# Sheet2.net
KiCad netlist of a schematic drawn in Altium Designer
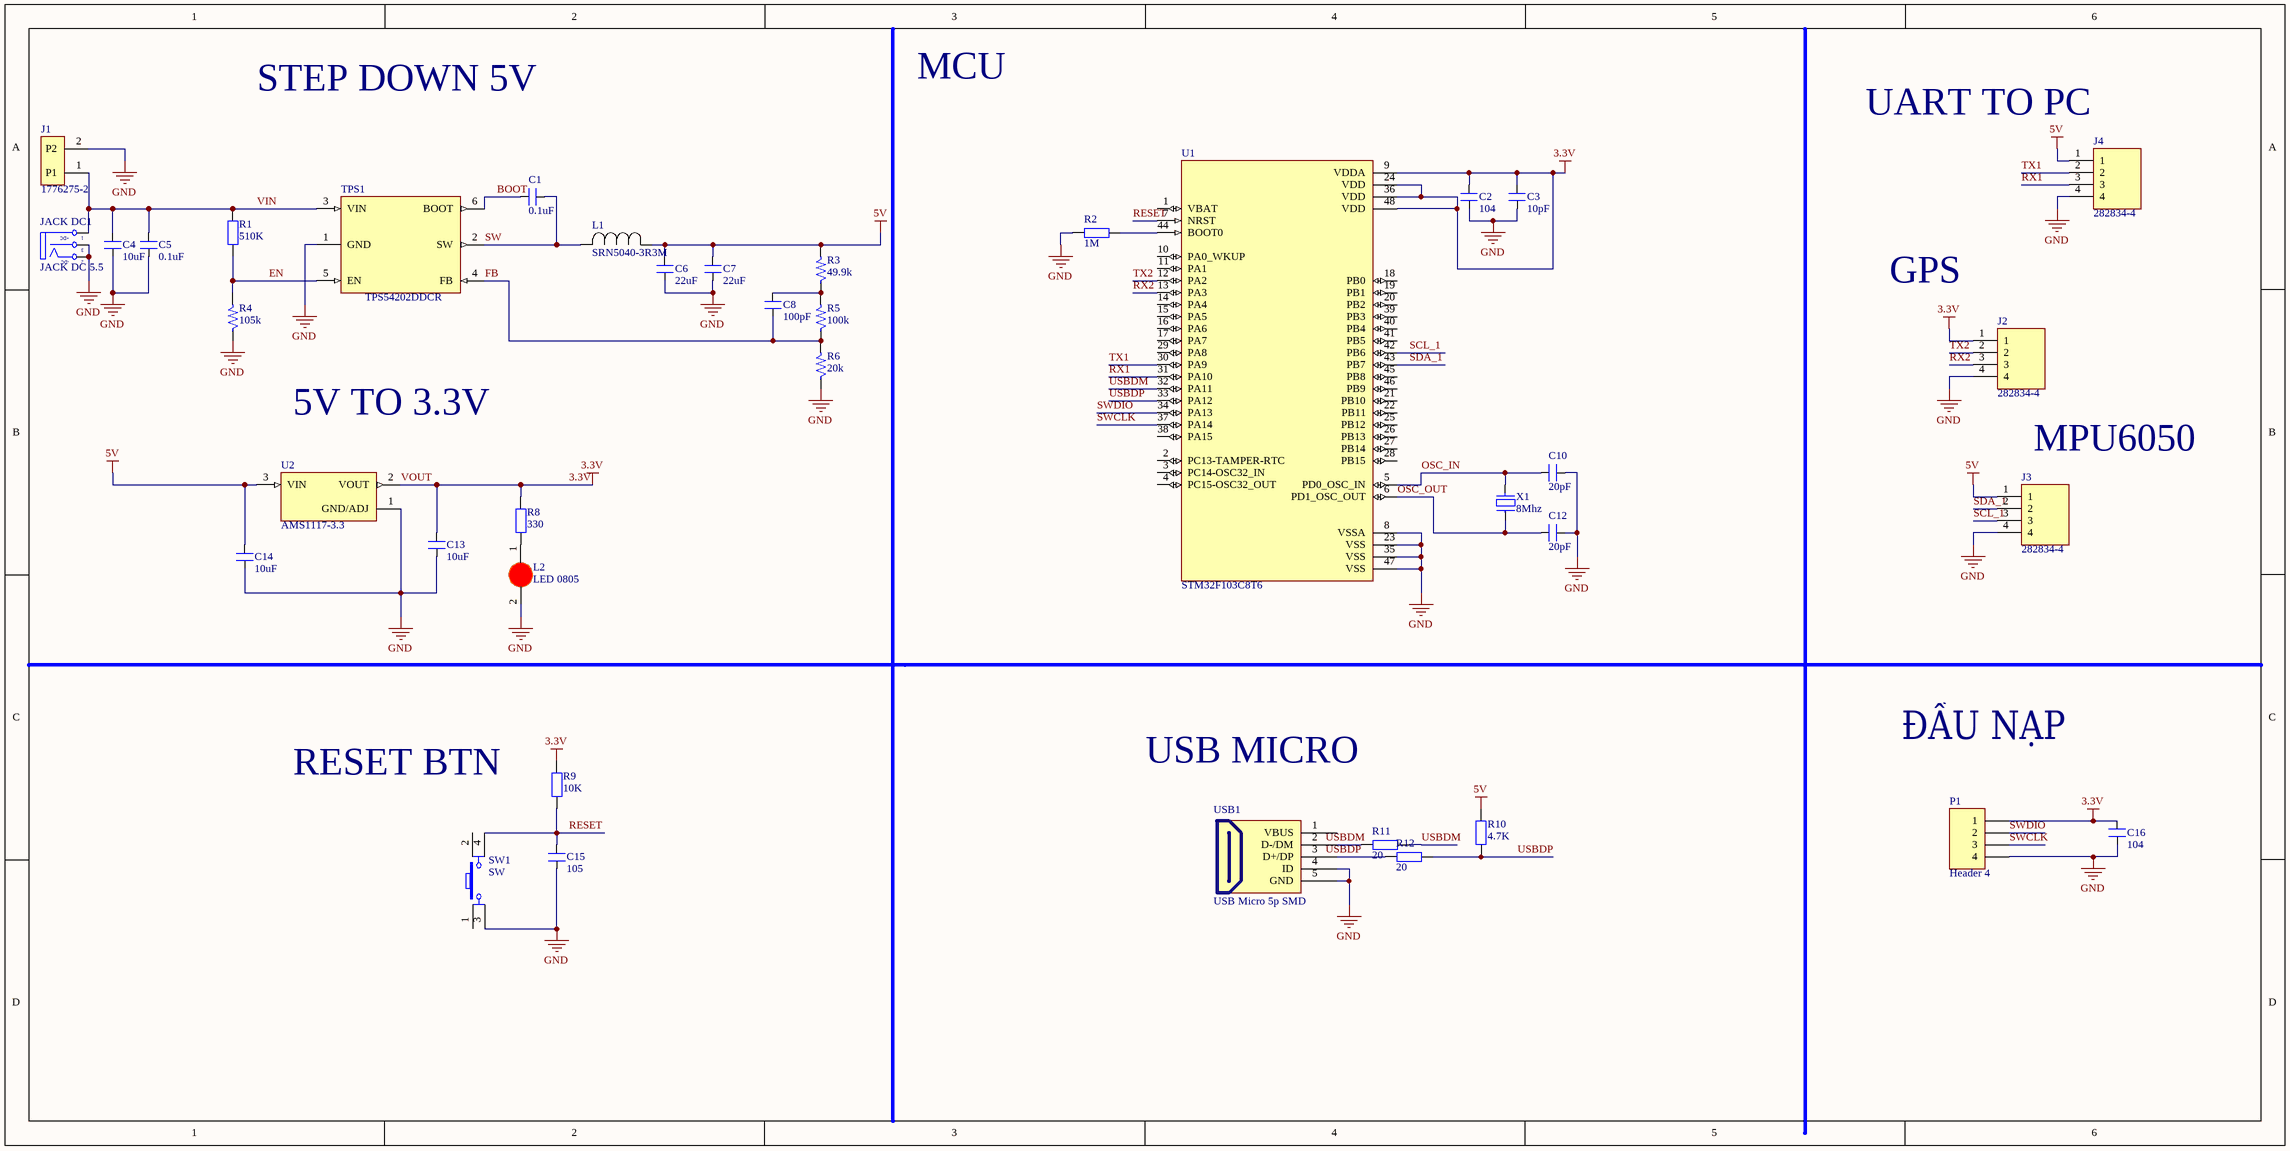
[diagram p0: Sheet2.SchDoc]

(export (version "E")
  (design (tool "Eeschema 10.0.6"))
  (components
    (comp (ref "C1")
      (value "0.1uF")
      (footprint "SM-0805")
      (description "Cap SMD")
      (libsource (lib "syhaunguyen") (part "CM"))
    )
    (comp (ref "C2")
      (value "104")
      (footprint "SM-0805")
      (description "Cap SMD")
      (libsource (lib "syhaunguyen") (part "CM"))
    )
    (comp (ref "C3")
      (value "10pF")
      (footprint "SM-0805")
      (description "Cap SMD")
      (libsource (lib "syhaunguyen") (part "CM"))
    )
    (comp (ref "C4")
      (value "10uF")
      (footprint "SM-0805")
      (description "Cap SMD")
      (libsource (lib "syhaunguyen") (part "CM"))
    )
    (comp (ref "C5")
      (value "0.1uF")
      (footprint "SM-0805")
      (description "Cap SMD")
      (libsource (lib "syhaunguyen") (part "CM"))
    )
    (comp (ref "C6")
      (value "22uF")
      (footprint "SM-0805")
      (description "Cap SMD")
      (libsource (lib "syhaunguyen") (part "CM"))
    )
    (comp (ref "C7")
      (value "22uF")
      (footprint "SM-0805")
      (description "Cap SMD")
      (libsource (lib "syhaunguyen") (part "CM"))
    )
    (comp (ref "C8")
      (value "100pF")
      (footprint "SM-0805")
      (description "Cap SMD")
      (libsource (lib "syhaunguyen") (part "CM"))
    )
    (comp (ref "C10")
      (value "20pF")
      (footprint "SM-0805")
      (description "Cap SMD")
      (libsource (lib "syhaunguyen") (part "CM"))
    )
    (comp (ref "C12")
      (value "20pF")
      (footprint "SM-0805")
      (description "Cap SMD")
      (libsource (lib "syhaunguyen") (part "CM"))
    )
    (comp (ref "C13")
      (value "10uF")
      (footprint "SM-0805")
      (description "Cap SMD")
      (libsource (lib "syhaunguyen") (part "CM"))
    )
    (comp (ref "C14")
      (value "10uF")
      (footprint "SM-0805")
      (description "Cap SMD")
      (libsource (lib "syhaunguyen") (part "CM"))
    )
    (comp (ref "C15")
      (value "105")
      (footprint "SM-0805")
      (description "Cap SMD")
      (libsource (lib "syhaunguyen") (part "CM"))
    )
    (comp (ref "C16")
      (value "104")
      (footprint "SM-0805")
      (description "Cap SMD")
      (libsource (lib "syhaunguyen") (part "CM"))
    )
    (comp (ref "J1")
      (value "1776275-2")
      (footprint "TE_1776275-2")
      (description "2 Position Wire to Board Terminal Block Horizontal with Board 0.138\" (3.50mm) Through Hole")
      (fields (field (name "MF") "TE Connectivity"))
      (libsource (lib "1776275-2") (part "1776275-2"))
    )
    (comp (ref "J2")
      (value "282834-4")
      (footprint "TE_282834-4")
      (description "4 Position Wire to Board Terminal Block Horizontal with Board 0.100 (2.54mm) Through Hole")
      (fields (field (name "MF") "TE Connectivity"))
      (libsource (lib "282834-4") (part "282834-4"))
    )
    (comp (ref "J3")
      (value "282834-4")
      (footprint "TE_282834-4")
      (description "4 Position Wire to Board Terminal Block Horizontal with Board 0.100 (2.54mm) Through Hole")
      (fields (field (name "MF") "TE Connectivity"))
      (libsource (lib "282834-4") (part "282834-4"))
    )
    (comp (ref "J4")
      (value "282834-4")
      (footprint "TE_282834-4")
      (description "4 Position Wire to Board Terminal Block Horizontal with Board 0.100 (2.54mm) Through Hole")
      (fields (field (name "MF") "TE Connectivity"))
      (libsource (lib "282834-4") (part "282834-4"))
    )
    (comp (ref "JACK DC1")
      (value "JACK DC 5.5")
      (footprint "JACK DC 5.5")
      (libsource (lib "Altium_Lib_by_KhueNguyenCreator") (part "JACK DC 5.5"))
    )
    (comp (ref "L1")
      (value "SRN5040-3R3M")
      (footprint "IND_SRN5040_BRN")
      (description "No Description Available")
      (libsource (lib "SRN5040-3R3M") (part "SRN5040-3R3M"))
    )
    (comp (ref "L2")
      (value "LED 0805")
      (footprint "LED-0805-Red")
      (description "Dán")
      (libsource (lib "Altium_Lib_by_KhueNguyenCreator") (part "LED 0805 Do"))
    )
    (comp (ref "P1")
      (value "Header 4")
      (footprint "HDR1X4")
      (description "Header, 4-Pin")
      (fields (field (name "PUBLISHER") "Altium Limited"))
      (libsource (lib "Miscellaneous Connectors") (part "Header 4"))
    )
    (comp (ref "R1")
      (value "510K")
      (footprint "SM-0805")
      (description "Resistor SMD")
      (libsource (lib "syhaunguyen") (part "RM"))
    )
    (comp (ref "R2")
      (value "1M")
      (footprint "0805 res")
      (description "Resistor SMD")
      (libsource (lib "syhaunguyen") (part "RM"))
    )
    (comp (ref "R3")
      (value "49.9k")
      (footprint "0805 res")
      (description "Resistor 1/4W")
      (libsource (lib "syhaunguyen") (part "res0805"))
    )
    (comp (ref "R4")
      (value "105k")
      (footprint "0805 res")
      (description "Resistor 1/4W")
      (libsource (lib "syhaunguyen") (part "res0805"))
    )
    (comp (ref "R5")
      (value "100k")
      (footprint "0805 res")
      (description "Resistor 1/4W")
      (libsource (lib "syhaunguyen") (part "res0805"))
    )
    (comp (ref "R6")
      (value "20k")
      (footprint "0805 res")
      (description "Resistor 1/4W")
      (libsource (lib "syhaunguyen") (part "res0805"))
    )
    (comp (ref "R8")
      (value "330")
      (footprint "0805 res")
      (description "Resistor SMD")
      (libsource (lib "syhaunguyen") (part "RM"))
    )
    (comp (ref "R9")
      (value "10K")
      (footprint "0805 res")
      (description "Resistor SMD")
      (libsource (lib "syhaunguyen") (part "RM"))
    )
    (comp (ref "R10")
      (value "4.7K")
      (footprint "0805 res")
      (description "Resistor SMD")
      (libsource (lib "syhaunguyen") (part "RM"))
    )
    (comp (ref "R11")
      (value "20")
      (footprint "0805 res")
      (description "Resistor SMD")
      (libsource (lib "syhaunguyen") (part "RM"))
    )
    (comp (ref "R12")
      (value "20")
      (footprint "0805 res")
      (description "Resistor SMD")
      (libsource (lib "syhaunguyen") (part "RM"))
    )
    (comp (ref "SW1")
      (value "SW")
      (footprint "SW4")
      (description "Switch button 4 pin")
      (libsource (lib "syhaunguyen") (part "SW4"))
    )
    (comp (ref "TPS1")
      (value "TPS54202DDCR")
      (footprint "SOT95P280X110-6N")
      (fields
        (field (name "MF") "Texas Instruments")
        (field (name "BUYPART") "https://www.snapeda.com/parts/TPS54202DDCR/Texas%20Instruments/view-part/565860/?ref=eda")
      )
      (libsource (lib "TPS54202DDCR") (part "TPS54202DDCR"))
    )
    (comp (ref "U1")
      (value "STM32F103C8T6")
      (footprint "QFP50P900X900X160-48N")
      (description "ARM® Cortex®-M3 STM32F1 Microcontroller IC 32-Bit 72MHz 64KB (64K x 8) FLASH 48-LQFP (7x7)")
      (fields (field (name "MF") "STMicroelectronics"))
      (libsource (lib "STM32F103C8T6") (part "STM32F103C8T6"))
    )
    (comp (ref "U2")
      (value "AMS1117-3.3")
      (footprint "SOT229P700X180-4N")
      (description "Sot223/Pkg 1-Amp 3.3-Volt Low Drop Out Voltage Regulatator")
      (fields (field (name "MF") "Advanced Monolithic Systems"))
      (libsource (lib "AMS1117-3.3") (part "AMS1117-3.3"))
    )
    (comp (ref "USB1")
      (value "USB Micro 5p SMD")
      (footprint "USB Micro 5p SMD")
      (description "USB Type B")
      (libsource (lib "Altium_Lib_by_KhueNguyenCreator") (part "USB Micro 5p SMD"))
    )
    (comp (ref "X1")
      (value "8Mhz")
      (footprint "VioletofSun:XT2")
      (description "Crystal For all Crystal 2pin.")
      (libsource (lib "VioletofSun") (part "XT2"))
    )
  )
  (nets
    (net (code "1") (name "/BOOT") (class "Default")
      (node (ref "C1") (pin "2") (pinfunction "2_2") (pintype "passive"))
      (node (ref "TPS1") (pin "6") (pinfunction "BOOT_6") (pintype "output"))
    )
    (net (code "2") (name "/EN") (class "Default")
      (node (ref "R1") (pin "2") (pinfunction "2_2") (pintype "passive"))
      (node (ref "R4") (pin "2") (pinfunction "2_2") (pintype "passive"))
      (node (ref "TPS1") (pin "5") (pinfunction "EN_5") (pintype "input"))
    )
    (net (code "3") (name "/FB") (class "Default")
      (node (ref "C8") (pin "1") (pinfunction "1_1") (pintype "passive"))
      (node (ref "R5") (pin "1") (pinfunction "1_1") (pintype "passive"))
      (node (ref "R6") (pin "2") (pinfunction "2_2") (pintype "passive"))
      (node (ref "TPS1") (pin "4") (pinfunction "FB_4") (pintype "input"))
    )
    (net (code "4") (name "/OSC_IN") (class "Default")
      (node (ref "C10") (pin "2") (pinfunction "2_2") (pintype "passive"))
      (node (ref "U1") (pin "5") (pinfunction "PD0_OSC_IN_5") (pintype "bidirectional"))
      (node (ref "X1") (pin "2") (pinfunction "2_2") (pintype "passive"))
    )
    (net (code "5") (name "/OSC_OUT") (class "Default")
      (node (ref "C12") (pin "2") (pinfunction "2_2") (pintype "passive"))
      (node (ref "U1") (pin "6") (pinfunction "PD1_OSC_OUT_6") (pintype "bidirectional"))
      (node (ref "X1") (pin "1") (pinfunction "1_1") (pintype "passive"))
    )
    (net (code "6") (name "/RESET") (class "Default")
      (node (ref "C15") (pin "2") (pinfunction "2_2") (pintype "passive"))
      (node (ref "R9") (pin "1") (pinfunction "1_1") (pintype "passive"))
      (node (ref "SW1") (pin "4") (pintype "passive"))
      (node (ref "U1") (pin "7") (pinfunction "NRST_7") (pintype "input"))
    )
    (net (code "7") (name "/RX1") (class "Default")
      (node (ref "J4") (pin "3") (pinfunction "3_3") (pintype "passive"))
      (node (ref "U1") (pin "31") (pinfunction "PA10_31") (pintype "bidirectional"))
    )
    (net (code "8") (name "/RX2") (class "Default")
      (node (ref "J2") (pin "3") (pinfunction "3_3") (pintype "passive"))
      (node (ref "U1") (pin "13") (pinfunction "PA3_13") (pintype "bidirectional"))
    )
    (net (code "9") (name "/SCL_1") (class "Default")
      (node (ref "J3") (pin "3") (pinfunction "3_3") (pintype "passive"))
      (node (ref "U1") (pin "42") (pinfunction "PB6_42") (pintype "bidirectional"))
    )
    (net (code "10") (name "/SDA_1") (class "Default")
      (node (ref "J3") (pin "2") (pinfunction "2_2") (pintype "passive"))
      (node (ref "U1") (pin "43") (pinfunction "PB7_43") (pintype "bidirectional"))
    )
    (net (code "11") (name "/SW") (class "Default")
      (node (ref "C1") (pin "1") (pinfunction "1_1") (pintype "passive"))
      (node (ref "L1") (pin "2") (pinfunction "2_2") (pintype "passive"))
      (node (ref "TPS1") (pin "2") (pinfunction "SW_2") (pintype "output"))
    )
    (net (code "12") (name "/SWCLK") (class "Default")
      (node (ref "P1") (pin "3") (pinfunction "3_3") (pintype "passive"))
      (node (ref "U1") (pin "37") (pinfunction "PA14_37") (pintype "bidirectional"))
    )
    (net (code "13") (name "/SWDIO") (class "Default")
      (node (ref "P1") (pin "2") (pinfunction "2_2") (pintype "passive"))
      (node (ref "U1") (pin "34") (pinfunction "PA13_34") (pintype "bidirectional"))
    )
    (net (code "14") (name "/TX1") (class "Default")
      (node (ref "J4") (pin "2") (pinfunction "2_2") (pintype "passive"))
      (node (ref "U1") (pin "30") (pinfunction "PA9_30") (pintype "bidirectional"))
    )
    (net (code "15") (name "/TX2") (class "Default")
      (node (ref "J2") (pin "2") (pinfunction "2_2") (pintype "passive"))
      (node (ref "U1") (pin "12") (pinfunction "PA2_12") (pintype "bidirectional"))
    )
    (net (code "16") (name "/USBDM") (class "Default")
      (node (ref "R11") (pin "2") (pinfunction "2_2") (pintype "passive"))
      (node (ref "U1") (pin "32") (pinfunction "PA11_32") (pintype "bidirectional"))
    )
    (net (code "17") (name "/USBDP") (class "Default")
      (node (ref "R10") (pin "1") (pinfunction "1_1") (pintype "passive"))
      (node (ref "R12") (pin "2") (pinfunction "2_2") (pintype "passive"))
      (node (ref "U1") (pin "33") (pinfunction "PA12_33") (pintype "bidirectional"))
    )
    (net (code "18") (name "/VIN") (class "Default")
      (node (ref "C4") (pin "2") (pinfunction "2_2") (pintype "passive"))
      (node (ref "C5") (pin "2") (pinfunction "2_2") (pintype "passive"))
      (node (ref "J1") (pin "1") (pinfunction "P1_1") (pintype "passive"))
      (node (ref "JACK DC1") (pin "1") (pinfunction "T_1") (pintype "passive"))
      (node (ref "R1") (pin "1") (pinfunction "1_1") (pintype "passive"))
      (node (ref "TPS1") (pin "3") (pinfunction "VIN_3") (pintype "input"))
    )
    (net (code "19") (name "3.3V") (class "Default")
      (node (ref "C13") (pin "2") (pinfunction "2_2") (pintype "passive"))
      (node (ref "C16") (pin "1") (pinfunction "1_1") (pintype "passive"))
      (node (ref "C2") (pin "2") (pinfunction "2_2") (pintype "passive"))
      (node (ref "C3") (pin "2") (pinfunction "2_2") (pintype "passive"))
      (node (ref "J2") (pin "1") (pinfunction "1_1") (pintype "passive"))
      (node (ref "P1") (pin "1") (pinfunction "1_1") (pintype "passive"))
      (node (ref "R8") (pin "2") (pinfunction "2_2") (pintype "passive"))
      (node (ref "R9") (pin "2") (pinfunction "2_2") (pintype "passive"))
      (node (ref "U1") (pin "24") (pinfunction "VDD_24") (pintype "power_in"))
      (node (ref "U1") (pin "36") (pinfunction "VDD_36") (pintype "power_in"))
      (node (ref "U1") (pin "48") (pinfunction "VDD_48") (pintype "power_in"))
      (node (ref "U1") (pin "9") (pinfunction "VDDA_9") (pintype "power_in"))
      (node (ref "U2") (pin "2") (pinfunction "VOUT_2") (pintype "output"))
    )
    (net (code "20") (name "5V") (class "Default")
      (node (ref "C14") (pin "2") (pinfunction "2_2") (pintype "passive"))
      (node (ref "C6") (pin "2") (pinfunction "2_2") (pintype "passive"))
      (node (ref "C7") (pin "2") (pinfunction "2_2") (pintype "passive"))
      (node (ref "J3") (pin "1") (pinfunction "1_1") (pintype "passive"))
      (node (ref "J4") (pin "1") (pinfunction "1_1") (pintype "passive"))
      (node (ref "L1") (pin "1") (pinfunction "1_1") (pintype "passive"))
      (node (ref "R10") (pin "2") (pinfunction "2_2") (pintype "passive"))
      (node (ref "R3") (pin "2") (pinfunction "2_2") (pintype "passive"))
      (node (ref "U2") (pin "3") (pinfunction "VIN_3") (pintype "input"))
    )
    (net (code "21") (name "GND") (class "Default")
      (node (ref "C10") (pin "1") (pinfunction "1_1") (pintype "passive"))
      (node (ref "C12") (pin "1") (pinfunction "1_1") (pintype "passive"))
      (node (ref "C13") (pin "1") (pinfunction "1_1") (pintype "passive"))
      (node (ref "C14") (pin "1") (pinfunction "1_1") (pintype "passive"))
      (node (ref "C15") (pin "1") (pinfunction "1_1") (pintype "passive"))
      (node (ref "C16") (pin "2") (pinfunction "2_2") (pintype "passive"))
      (node (ref "C2") (pin "1") (pinfunction "1_1") (pintype "passive"))
      (node (ref "C3") (pin "1") (pinfunction "1_1") (pintype "passive"))
      (node (ref "C4") (pin "1") (pinfunction "1_1") (pintype "passive"))
      (node (ref "C5") (pin "1") (pinfunction "1_1") (pintype "passive"))
      (node (ref "C6") (pin "1") (pinfunction "1_1") (pintype "passive"))
      (node (ref "C7") (pin "1") (pinfunction "1_1") (pintype "passive"))
      (node (ref "J1") (pin "2") (pinfunction "P2_2") (pintype "passive"))
      (node (ref "J2") (pin "4") (pinfunction "4_4") (pintype "passive"))
      (node (ref "J3") (pin "4") (pinfunction "4_4") (pintype "passive"))
      (node (ref "J4") (pin "4") (pinfunction "4_4") (pintype "passive"))
      (node (ref "JACK DC1") (pin "2") (pinfunction "TN_2") (pintype "passive"))
      (node (ref "JACK DC1") (pin "3") (pinfunction "S_3") (pintype "power_in"))
      (node (ref "L2") (pin "2") (pinfunction "K_2") (pintype "passive"))
      (node (ref "P1") (pin "4") (pinfunction "4_4") (pintype "passive"))
      (node (ref "R2") (pin "1") (pinfunction "1_1") (pintype "passive"))
      (node (ref "R4") (pin "1") (pinfunction "1_1") (pintype "passive"))
      (node (ref "R6") (pin "1") (pinfunction "1_1") (pintype "passive"))
      (node (ref "SW1") (pin "3") (pintype "passive"))
      (node (ref "TPS1") (pin "1") (pinfunction "GND_1") (pintype "power_in"))
      (node (ref "U1") (pin "23") (pinfunction "VSS_23") (pintype "power_in"))
      (node (ref "U1") (pin "35") (pinfunction "VSS_35") (pintype "power_in"))
      (node (ref "U1") (pin "47") (pinfunction "VSS_47") (pintype "power_in"))
      (node (ref "U1") (pin "8") (pinfunction "VSSA_8") (pintype "power_in"))
      (node (ref "U2") (pin "1") (pinfunction "GND/ADJ_1") (pintype "power_in"))
      (node (ref "USB1") (pin "4") (pinfunction "ID_4") (pintype "passive"))
      (node (ref "USB1") (pin "5") (pinfunction "GND_5") (pintype "passive"))
    )
    (net (code "22") (name "Net-(C8-Pad2)") (class "Default")
      (node (ref "C8") (pin "2") (pinfunction "2_2") (pintype "passive"))
      (node (ref "R3") (pin "1") (pinfunction "1_1") (pintype "passive"))
      (node (ref "R5") (pin "2") (pinfunction "2_2") (pintype "passive"))
    )
    (net (code "23") (name "Net-(L2-A)") (class "Default")
      (node (ref "L2") (pin "1") (pinfunction "A_1") (pintype "passive"))
      (node (ref "R8") (pin "1") (pinfunction "1_1") (pintype "passive"))
    )
    (net (code "24") (name "Net-(U1-BOOT0)") (class "Default")
      (node (ref "R2") (pin "2") (pinfunction "2_2") (pintype "passive"))
      (node (ref "U1") (pin "44") (pinfunction "BOOT0_44") (pintype "input"))
    )
    (net (code "25") (name "Net-(USB1-D+{slash}DP)") (class "Default")
      (node (ref "R12") (pin "1") (pinfunction "1_1") (pintype "passive"))
      (node (ref "USB1") (pin "3") (pinfunction "D+/DP_3") (pintype "passive"))
    )
    (net (code "26") (name "Net-(USB1-D-{slash}DM)") (class "Default")
      (node (ref "R11") (pin "1") (pinfunction "1_1") (pintype "passive"))
      (node (ref "USB1") (pin "2") (pinfunction "D-/DM_2") (pintype "passive"))
    )
    (net (code "27") (name "unconnected-(SW1-Pad1)") (class "Default")
      (node (ref "SW1") (pin "1") (pintype "passive"))
    )
    (net (code "28") (name "unconnected-(SW1-Pad2)") (class "Default")
      (node (ref "SW1") (pin "2") (pintype "passive"))
    )
    (net (code "29") (name "unconnected-(U1-PA0_WKUP-Pad10)") (class "Default")
      (node (ref "U1") (pin "10") (pinfunction "PA0_WKUP_10") (pintype "bidirectional"))
    )
    (net (code "30") (name "unconnected-(U1-PA1-Pad11)") (class "Default")
      (node (ref "U1") (pin "11") (pinfunction "PA1_11") (pintype "bidirectional"))
    )
    (net (code "31") (name "unconnected-(U1-PA4-Pad14)") (class "Default")
      (node (ref "U1") (pin "14") (pinfunction "PA4_14") (pintype "bidirectional"))
    )
    (net (code "32") (name "unconnected-(U1-PA5-Pad15)") (class "Default")
      (node (ref "U1") (pin "15") (pinfunction "PA5_15") (pintype "bidirectional"))
    )
    (net (code "33") (name "unconnected-(U1-PA6-Pad16)") (class "Default")
      (node (ref "U1") (pin "16") (pinfunction "PA6_16") (pintype "bidirectional"))
    )
    (net (code "34") (name "unconnected-(U1-PA7-Pad17)") (class "Default")
      (node (ref "U1") (pin "17") (pinfunction "PA7_17") (pintype "bidirectional"))
    )
    (net (code "35") (name "unconnected-(U1-PA8-Pad29)") (class "Default")
      (node (ref "U1") (pin "29") (pinfunction "PA8_29") (pintype "bidirectional"))
    )
    (net (code "36") (name "unconnected-(U1-PA15-Pad38)") (class "Default")
      (node (ref "U1") (pin "38") (pinfunction "PA15_38") (pintype "bidirectional"))
    )
    (net (code "37") (name "unconnected-(U1-PB0-Pad18)") (class "Default")
      (node (ref "U1") (pin "18") (pinfunction "PB0_18") (pintype "bidirectional"))
    )
    (net (code "38") (name "unconnected-(U1-PB1-Pad19)") (class "Default")
      (node (ref "U1") (pin "19") (pinfunction "PB1_19") (pintype "bidirectional"))
    )
    (net (code "39") (name "unconnected-(U1-PB2-Pad20)") (class "Default")
      (node (ref "U1") (pin "20") (pinfunction "PB2_20") (pintype "bidirectional"))
    )
    (net (code "40") (name "unconnected-(U1-PB3-Pad39)") (class "Default")
      (node (ref "U1") (pin "39") (pinfunction "PB3_39") (pintype "bidirectional"))
    )
    (net (code "41") (name "unconnected-(U1-PB4-Pad40)") (class "Default")
      (node (ref "U1") (pin "40") (pinfunction "PB4_40") (pintype "bidirectional"))
    )
    (net (code "42") (name "unconnected-(U1-PB5-Pad41)") (class "Default")
      (node (ref "U1") (pin "41") (pinfunction "PB5_41") (pintype "bidirectional"))
    )
    (net (code "43") (name "unconnected-(U1-PB8-Pad45)") (class "Default")
      (node (ref "U1") (pin "45") (pinfunction "PB8_45") (pintype "bidirectional"))
    )
    (net (code "44") (name "unconnected-(U1-PB9-Pad46)") (class "Default")
      (node (ref "U1") (pin "46") (pinfunction "PB9_46") (pintype "bidirectional"))
    )
    (net (code "45") (name "unconnected-(U1-PB10-Pad21)") (class "Default")
      (node (ref "U1") (pin "21") (pinfunction "PB10_21") (pintype "bidirectional"))
    )
    (net (code "46") (name "unconnected-(U1-PB11-Pad22)") (class "Default")
      (node (ref "U1") (pin "22") (pinfunction "PB11_22") (pintype "bidirectional"))
    )
    (net (code "47") (name "unconnected-(U1-PB12-Pad25)") (class "Default")
      (node (ref "U1") (pin "25") (pinfunction "PB12_25") (pintype "bidirectional"))
    )
    (net (code "48") (name "unconnected-(U1-PB13-Pad26)") (class "Default")
      (node (ref "U1") (pin "26") (pinfunction "PB13_26") (pintype "bidirectional"))
    )
    (net (code "49") (name "unconnected-(U1-PB14-Pad27)") (class "Default")
      (node (ref "U1") (pin "27") (pinfunction "PB14_27") (pintype "bidirectional"))
    )
    (net (code "50") (name "unconnected-(U1-PB15-Pad28)") (class "Default")
      (node (ref "U1") (pin "28") (pinfunction "PB15_28") (pintype "bidirectional"))
    )
    (net (code "51") (name "unconnected-(U1-PC13-TAMPER-RTC-Pad2)") (class "Default")
      (node (ref "U1") (pin "2") (pinfunction "PC13-TAMPER-RTC_2") (pintype "bidirectional"))
    )
    (net (code "52") (name "unconnected-(U1-PC14-OSC32_IN-Pad3)") (class "Default")
      (node (ref "U1") (pin "3") (pinfunction "PC14-OSC32_IN_3") (pintype "bidirectional"))
    )
    (net (code "53") (name "unconnected-(U1-PC15-OSC32_OUT-Pad4)") (class "Default")
      (node (ref "U1") (pin "4") (pinfunction "PC15-OSC32_OUT_4") (pintype "bidirectional"))
    )
    (net (code "54") (name "unconnected-(U1-VBAT-Pad1)") (class "Default")
      (node (ref "U1") (pin "1") (pinfunction "VBAT_1") (pintype "bidirectional"))
    )
    (net (code "55") (name "unconnected-(USB1-VBUS-Pad1)") (class "Default")
      (node (ref "USB1") (pin "1") (pinfunction "VBUS_1") (pintype "passive"))
    )
  )
)
